# keyring.net
KiCad netlist of a schematic drawn in EAGLE
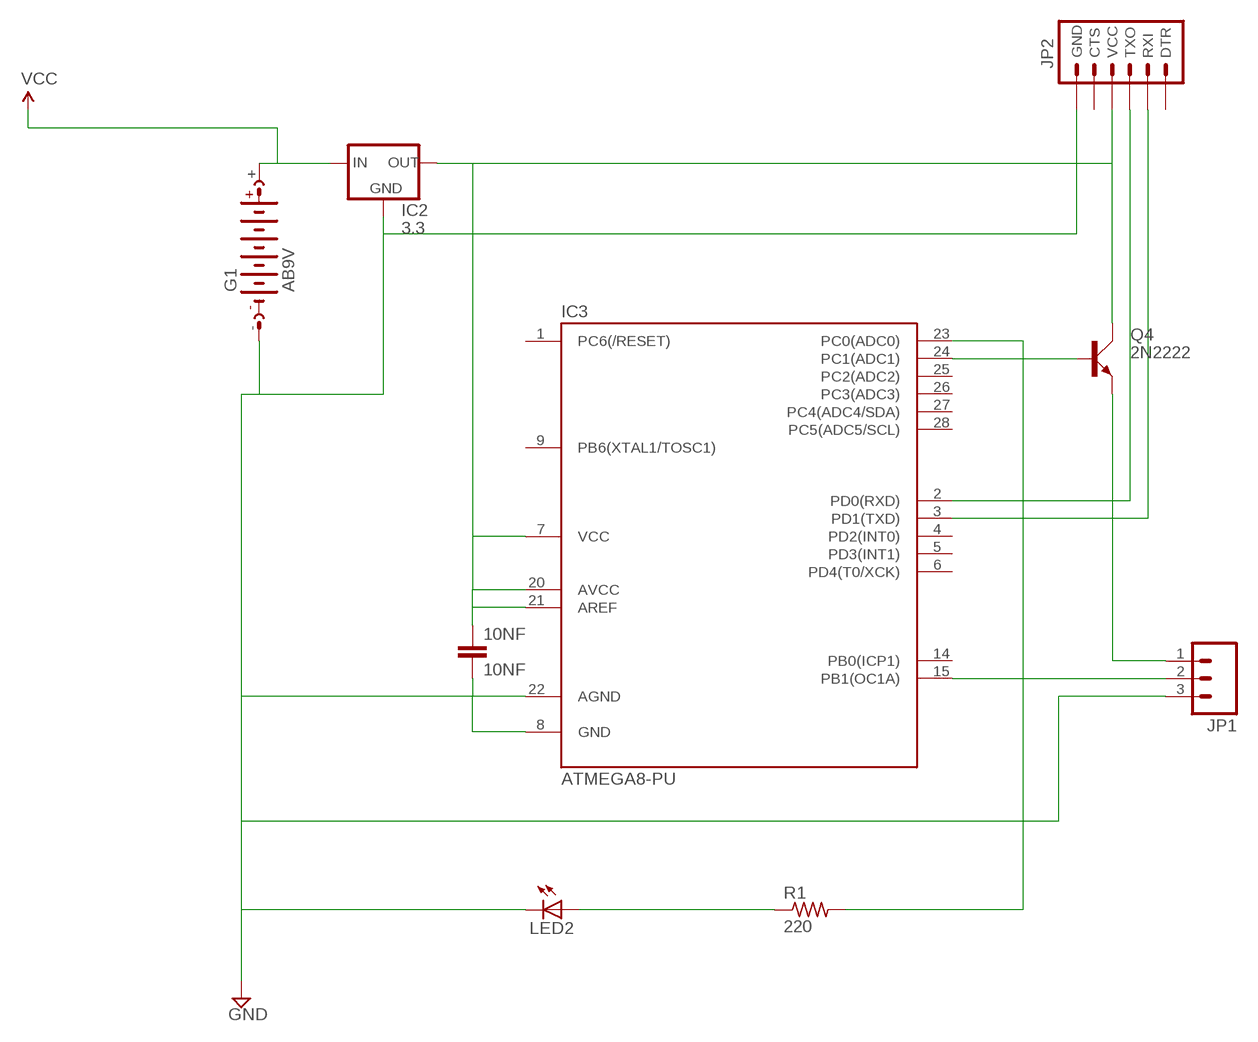
[diagram p0: schematic, sheet 1]

(export (version "E")
  (design (tool "Eeschema 10.0.6"))
  (components
    (comp (ref "10NF")
      (value "10NF")
      (footprint "eagle-import:C2.5-4")
      (libsource (lib "eagle-import") (part "C2.5/4"))
    )
    (comp (ref "G1")
      (value "AB9V")
      (footprint "eagle-import:AB9V")
      (libsource (lib "eagle-import") (part "AB9V"))
    )
    (comp (ref "IC2")
      (value "3.3")
      (footprint "eagle-import:TO220-IGO")
      (libsource (lib "eagle-import") (part "V_REG_78XXSINK"))
    )
    (comp (ref "IC3")
      (value "ATMEGA8-PU")
      (footprint "eagle-import:DIL28-3")
      (libsource (lib "eagle-import") (part "ATMEGA8-PU"))
    )
    (comp (ref "JP1")
      (value "M03LONGPADS")
      (footprint "eagle-import:1X03_LONGPADS")
      (libsource (lib "eagle-import") (part "M03LONGPADS"))
    )
    (comp (ref "JP2")
      (value "ARDUINO_SERIAL_PROGRAMLONGPADS")
      (footprint "eagle-import:1X06_LONGPADS")
      (libsource (lib "eagle-import") (part "ARDUINO_SERIAL_PROGRAMLONGPADS"))
    )
    (comp (ref "LED2")
      (value "LED3MM")
      (footprint "eagle-import:LED3MM")
      (libsource (lib "eagle-import") (part "LED3MM"))
    )
    (comp (ref "Q4")
      (value "2N2222")
      (footprint "eagle-import:TO18A")
      (libsource (lib "eagle-import") (part "2N2222"))
    )
    (comp (ref "R1")
      (value "220")
      (footprint "eagle-import:0207_12")
      (libsource (lib "eagle-import") (part "R-US_0207/12"))
    )
  )
  (nets
    (net (code "1") (name "GND") (class "Default")
      (node (ref "10NF") (pin "2") (pinfunction "2_2") (pintype "passive"))
      (node (ref "G1") (pin "-") (pinfunction "-_-") (pintype "passive"))
      (node (ref "IC2") (pin "GND") (pinfunction "GND_GND") (pintype "input"))
      (node (ref "IC3") (pin "22") (pinfunction "AGND_22") (pintype "power_in"))
      (node (ref "IC3") (pin "8") (pinfunction "GND_8") (pintype "power_in"))
      (node (ref "JP1") (pin "3") (pinfunction "VCC_3") (pintype "passive"))
      (node (ref "JP2") (pin "6") (pinfunction "GND_6") (pintype "passive"))
      (node (ref "LED2") (pin "K") (pinfunction "C_K") (pintype "passive"))
    )
    (net (code "2") (name "Net-(IC3-AREF)") (class "Default")
      (node (ref "10NF") (pin "1") (pinfunction "1_1") (pintype "passive"))
      (node (ref "IC2") (pin "OUT") (pinfunction "OUT_OUT") (pintype "output"))
      (node (ref "IC3") (pin "20") (pinfunction "AVCC_20") (pintype "passive"))
      (node (ref "IC3") (pin "21") (pinfunction "AREF_21") (pintype "passive"))
      (node (ref "IC3") (pin "7") (pinfunction "VCC_7") (pintype "power_in"))
      (node (ref "JP2") (pin "4") (pinfunction "VCC_4") (pintype "passive"))
      (node (ref "Q4") (pin "C") (pinfunction "C_C") (pintype "passive"))
    )
    (net (code "3") (name "Net-(IC3-PB1(OC1A))") (class "Default")
      (node (ref "IC3") (pin "15") (pinfunction "PB1(OC1A)_15") (pintype "bidirectional"))
      (node (ref "JP1") (pin "2") (pinfunction "GND_2") (pintype "passive"))
    )
    (net (code "4") (name "Net-(IC3-PC0(ADC0))") (class "Default")
      (node (ref "IC3") (pin "23") (pinfunction "PC0(ADC0)_23") (pintype "bidirectional"))
      (node (ref "R1") (pin "2") (pinfunction "2_2") (pintype "passive"))
    )
    (net (code "5") (name "Net-(IC3-PC1(ADC1))") (class "Default")
      (node (ref "IC3") (pin "24") (pinfunction "PC1(ADC1)_24") (pintype "bidirectional"))
      (node (ref "Q4") (pin "B") (pinfunction "B_B") (pintype "passive"))
    )
    (net (code "6") (name "Net-(IC3-PD0(RXD))") (class "Default")
      (node (ref "IC3") (pin "2") (pinfunction "PD0(RXD)_2") (pintype "bidirectional"))
      (node (ref "JP2") (pin "3") (pinfunction "TXO_3") (pintype "passive"))
    )
    (net (code "7") (name "Net-(IC3-PD1(TXD))") (class "Default")
      (node (ref "IC3") (pin "3") (pinfunction "PD1(TXD)_3") (pintype "bidirectional"))
      (node (ref "JP2") (pin "2") (pinfunction "RXI_2") (pintype "passive"))
    )
    (net (code "8") (name "Net-(JP1-OUT)") (class "Default")
      (node (ref "JP1") (pin "1") (pinfunction "OUT_1") (pintype "passive"))
      (node (ref "Q4") (pin "E") (pinfunction "E_E") (pintype "passive"))
    )
    (net (code "9") (name "Net-(LED2-PadA)") (class "Default")
      (node (ref "LED2") (pin "A") (pinfunction "A_A") (pintype "passive"))
      (node (ref "R1") (pin "1") (pinfunction "1_1") (pintype "passive"))
    )
    (net (code "10") (name "VCC") (class "Default")
      (node (ref "G1") (pin "+") (pinfunction "+_+") (pintype "passive"))
      (node (ref "IC2") (pin "IN") (pinfunction "IN_IN") (pintype "input"))
    )
    (net (code "11") (name "unconnected-(IC3-PB0(ICP1)-Pad14)") (class "Default")
      (node (ref "IC3") (pin "14") (pinfunction "PB0(ICP1)_14") (pintype "bidirectional"))
    )
    (net (code "12") (name "unconnected-(IC3-PB6(XTAL1{slash}TOSC1)-Pad9)") (class "Default")
      (node (ref "IC3") (pin "9") (pinfunction "PB6(XTAL1/TOSC1)_9") (pintype "bidirectional"))
    )
    (net (code "13") (name "unconnected-(IC3-PC2(ADC2)-Pad25)") (class "Default")
      (node (ref "IC3") (pin "25") (pinfunction "PC2(ADC2)_25") (pintype "bidirectional"))
    )
    (net (code "14") (name "unconnected-(IC3-PC3(ADC3)-Pad26)") (class "Default")
      (node (ref "IC3") (pin "26") (pinfunction "PC3(ADC3)_26") (pintype "bidirectional"))
    )
    (net (code "15") (name "unconnected-(IC3-PC4(ADC4{slash}SDA)-Pad27)") (class "Default")
      (node (ref "IC3") (pin "27") (pinfunction "PC4(ADC4/SDA)_27") (pintype "bidirectional"))
    )
    (net (code "16") (name "unconnected-(IC3-PC5(ADC5{slash}SCL)-Pad28)") (class "Default")
      (node (ref "IC3") (pin "28") (pinfunction "PC5(ADC5/SCL)_28") (pintype "bidirectional"))
    )
    (net (code "17") (name "unconnected-(IC3-PC6({slash}RESET)-Pad1)") (class "Default")
      (node (ref "IC3") (pin "1") (pinfunction "PC6(/RESET)_1") (pintype "bidirectional"))
    )
    (net (code "18") (name "unconnected-(IC3-PD2(INT0)-Pad4)") (class "Default")
      (node (ref "IC3") (pin "4") (pinfunction "PD2(INT0)_4") (pintype "bidirectional"))
    )
    (net (code "19") (name "unconnected-(IC3-PD3(INT1)-Pad5)") (class "Default")
      (node (ref "IC3") (pin "5") (pinfunction "PD3(INT1)_5") (pintype "bidirectional"))
    )
    (net (code "20") (name "unconnected-(IC3-PD4(T0{slash}XCK)-Pad6)") (class "Default")
      (node (ref "IC3") (pin "6") (pinfunction "PD4(T0/XCK)_6") (pintype "bidirectional"))
    )
    (net (code "21") (name "unconnected-(JP2-CTS-Pad5)") (class "Default")
      (node (ref "JP2") (pin "5") (pinfunction "CTS_5") (pintype "passive"))
    )
    (net (code "22") (name "unconnected-(JP2-DTR-Pad1)") (class "Default")
      (node (ref "JP2") (pin "1") (pinfunction "DTR_1") (pintype "passive"))
    )
  )
)
